# app_out_8x_16A_bistab_seperated_4MU_BOT_.net
KiCad netlist of a schematic drawn in EAGLE
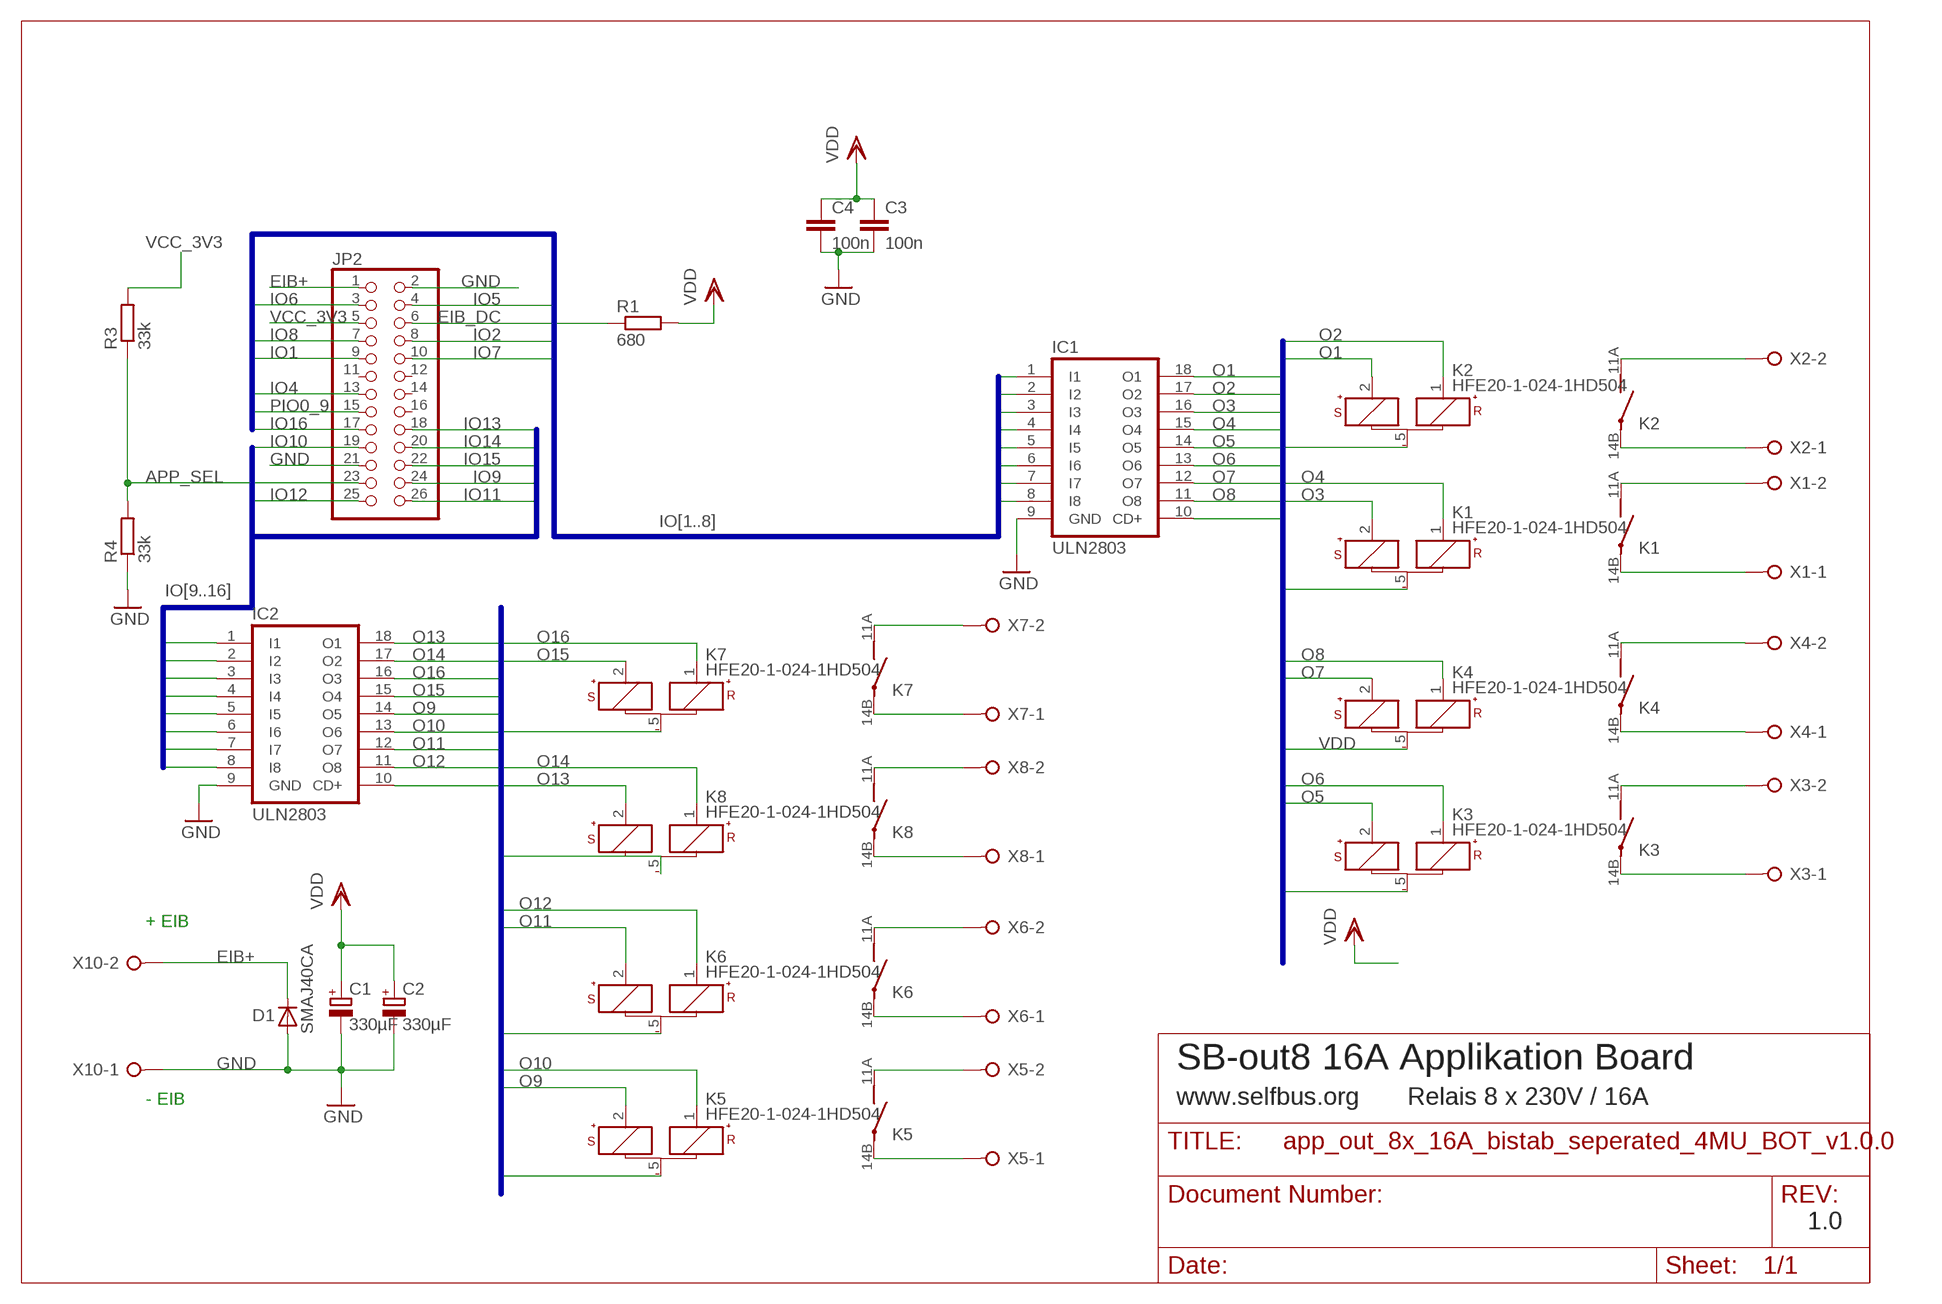
[diagram p0: schematic, sheet 1]

(export (version "E")
  (design (tool "Eeschema 10.0.6"))
  (components
    (comp (ref "C1")
      (value "330µF")
      (footprint "eagle-import:E3,5-8")
      (libsource (lib "eagle-import") (part "CPOL-EUE3.5-8"))
    )
    (comp (ref "C2")
      (value "330µF")
      (footprint "eagle-import:E3,5-8")
      (libsource (lib "eagle-import") (part "CPOL-EUE3.5-8"))
    )
    (comp (ref "C3")
      (value "100n")
      (footprint "eagle-import:C1206")
      (libsource (lib "eagle-import") (part "C-EUC1206"))
    )
    (comp (ref "C4")
      (value "100n")
      (footprint "eagle-import:C1206")
      (libsource (lib "eagle-import") (part "C-EUC1206"))
    )
    (comp (ref "D1")
      (value "SMAJ40CA")
      (footprint "eagle-import:SMB")
      (libsource (lib "eagle-import") (part "D-SMB"))
    )
    (comp (ref "IC1")
      (value "ULN2803")
      (footprint "eagle-import:SO18W")
      (libsource (lib "eagle-import") (part "ULN2803ASOP18"))
    )
    (comp (ref "IC2")
      (value "ULN2803")
      (footprint "eagle-import:SO18W")
      (libsource (lib "eagle-import") (part "ULN2803ASOP18"))
    )
    (comp (ref "JP2")
      (value "PINHD-2X13_2.54-SMD")
      (footprint "eagle-import:2X13SMD")
      (libsource (lib "eagle-import") (part "PINHD-2X13_2.54-SMD"))
    )
    (comp (ref "K1")
      (value "HFE20-1-024-1HD504")
      (footprint "eagle-import:HFE20-3-504")
      (libsource (lib "eagle-import") (part "HFE20-1-024-1HD504"))
    )
    (comp (ref "K2")
      (value "HFE20-1-024-1HD504")
      (footprint "eagle-import:HFE20-3-504")
      (libsource (lib "eagle-import") (part "HFE20-1-024-1HD504"))
    )
    (comp (ref "K3")
      (value "HFE20-1-024-1HD504")
      (footprint "eagle-import:HFE20-3-504")
      (libsource (lib "eagle-import") (part "HFE20-1-024-1HD504"))
    )
    (comp (ref "K4")
      (value "HFE20-1-024-1HD504")
      (footprint "eagle-import:HFE20-3-504")
      (libsource (lib "eagle-import") (part "HFE20-1-024-1HD504"))
    )
    (comp (ref "K5")
      (value "HFE20-1-024-1HD504")
      (footprint "eagle-import:HFE20-3-504")
      (libsource (lib "eagle-import") (part "HFE20-1-024-1HD504"))
    )
    (comp (ref "K6")
      (value "HFE20-1-024-1HD504")
      (footprint "eagle-import:HFE20-3-504")
      (libsource (lib "eagle-import") (part "HFE20-1-024-1HD504"))
    )
    (comp (ref "K7")
      (value "HFE20-1-024-1HD504")
      (footprint "eagle-import:HFE20-3-504")
      (libsource (lib "eagle-import") (part "HFE20-1-024-1HD504"))
    )
    (comp (ref "K8")
      (value "HFE20-1-024-1HD504")
      (footprint "eagle-import:HFE20-3-504")
      (libsource (lib "eagle-import") (part "HFE20-1-024-1HD504"))
    )
    (comp (ref "R1")
      (value "680")
      (footprint "eagle-import:M1206")
      (libsource (lib "eagle-import") (part "R-EU_M1206"))
    )
    (comp (ref "R3")
      (value "33k")
      (footprint "eagle-import:M1206")
      (libsource (lib "eagle-import") (part "R-EU_M1206"))
    )
    (comp (ref "R4")
      (value "33k")
      (footprint "eagle-import:M1206")
      (libsource (lib "eagle-import") (part "R-EU_M1206"))
    )
    (comp (ref "X1")
      (value "W237-02P")
      (footprint "eagle-import:W237-132")
      (libsource (lib "eagle-import") (part "W237-02P"))
    )
    (comp (ref "X2")
      (value "W237-02P")
      (footprint "eagle-import:W237-132")
      (libsource (lib "eagle-import") (part "W237-02P"))
    )
    (comp (ref "X3")
      (value "W237-02P")
      (footprint "eagle-import:W237-132")
      (libsource (lib "eagle-import") (part "W237-02P"))
    )
    (comp (ref "X4")
      (value "W237-02P")
      (footprint "eagle-import:W237-132")
      (libsource (lib "eagle-import") (part "W237-02P"))
    )
    (comp (ref "X5")
      (value "W237-02P")
      (footprint "eagle-import:W237-132")
      (libsource (lib "eagle-import") (part "W237-02P"))
    )
    (comp (ref "X6")
      (value "W237-02P")
      (footprint "eagle-import:W237-132")
      (libsource (lib "eagle-import") (part "W237-02P"))
    )
    (comp (ref "X7")
      (value "W237-02P")
      (footprint "eagle-import:W237-132")
      (libsource (lib "eagle-import") (part "W237-02P"))
    )
    (comp (ref "X8")
      (value "W237-02P")
      (footprint "eagle-import:W237-132")
      (libsource (lib "eagle-import") (part "W237-02P"))
    )
    (comp (ref "X10")
      (value "W237-02P")
      (footprint "eagle-import:W237-132")
      (libsource (lib "eagle-import") (part "W237-02P"))
    )
  )
  (nets
    (net (code "2") (name "/APP_SEL") (class "Default")
      (node (ref "JP2") (pin "23") (pinfunction "23_23") (pintype "passive"))
      (node (ref "R3") (pin "1") (pinfunction "1_1") (pintype "passive"))
      (node (ref "R4") (pin "2") (pinfunction "2_2") (pintype "passive"))
    )
    (net (code "3") (name "/EIB+") (class "Default")
      (node (ref "D1") (pin "1") (pinfunction "C_1") (pintype "passive"))
      (node (ref "JP2") (pin "1") (pinfunction "1_1") (pintype "passive"))
      (node (ref "X10") (pin "2") (pinfunction "KL_2") (pintype "passive"))
    )
    (net (code "4") (name "/EIB_DC") (class "Default")
      (node (ref "JP2") (pin "6") (pinfunction "6_6") (pintype "passive"))
      (node (ref "R1") (pin "1") (pinfunction "1_1") (pintype "passive"))
    )
    (net (code "5") (name "/IO1") (class "Default")
      (node (ref "IC1") (pin "5") (pinfunction "I5_5") (pintype "input"))
      (node (ref "JP2") (pin "9") (pinfunction "9_9") (pintype "passive"))
    )
    (net (code "6") (name "/IO2") (class "Default")
      (node (ref "IC1") (pin "4") (pinfunction "I4_4") (pintype "input"))
      (node (ref "JP2") (pin "8") (pinfunction "8_8") (pintype "passive"))
    )
    (net (code "7") (name "/IO4") (class "Default")
      (node (ref "IC1") (pin "8") (pinfunction "I8_8") (pintype "input"))
      (node (ref "JP2") (pin "13") (pinfunction "13_13") (pintype "passive"))
    )
    (net (code "8") (name "/IO5") (class "Default")
      (node (ref "IC1") (pin "1") (pinfunction "I1_1") (pintype "input"))
      (node (ref "JP2") (pin "4") (pinfunction "4_4") (pintype "passive"))
    )
    (net (code "9") (name "/IO6") (class "Default")
      (node (ref "IC1") (pin "2") (pinfunction "I2_2") (pintype "input"))
      (node (ref "JP2") (pin "3") (pinfunction "3_3") (pintype "passive"))
    )
    (net (code "10") (name "/IO7") (class "Default")
      (node (ref "IC1") (pin "6") (pinfunction "I6_6") (pintype "input"))
      (node (ref "JP2") (pin "10") (pinfunction "10_10") (pintype "passive"))
    )
    (net (code "11") (name "/IO8") (class "Default")
      (node (ref "IC1") (pin "3") (pinfunction "I3_3") (pintype "input"))
      (node (ref "JP2") (pin "7") (pinfunction "7_7") (pintype "passive"))
    )
    (net (code "12") (name "/IO9") (class "Default")
      (node (ref "IC2") (pin "5") (pinfunction "I5_5") (pintype "input"))
      (node (ref "JP2") (pin "24") (pinfunction "24_24") (pintype "passive"))
    )
    (net (code "13") (name "/IO10") (class "Default")
      (node (ref "IC2") (pin "6") (pinfunction "I6_6") (pintype "input"))
      (node (ref "JP2") (pin "19") (pinfunction "19_19") (pintype "passive"))
    )
    (net (code "14") (name "/IO11") (class "Default")
      (node (ref "IC2") (pin "7") (pinfunction "I7_7") (pintype "input"))
      (node (ref "JP2") (pin "26") (pinfunction "26_26") (pintype "passive"))
    )
    (net (code "15") (name "/IO12") (class "Default")
      (node (ref "IC2") (pin "8") (pinfunction "I8_8") (pintype "input"))
      (node (ref "JP2") (pin "25") (pinfunction "25_25") (pintype "passive"))
    )
    (net (code "16") (name "/IO13") (class "Default")
      (node (ref "IC2") (pin "1") (pinfunction "I1_1") (pintype "input"))
      (node (ref "JP2") (pin "18") (pinfunction "18_18") (pintype "passive"))
    )
    (net (code "17") (name "/IO14") (class "Default")
      (node (ref "IC2") (pin "2") (pinfunction "I2_2") (pintype "input"))
      (node (ref "JP2") (pin "20") (pinfunction "20_20") (pintype "passive"))
    )
    (net (code "18") (name "/IO15") (class "Default")
      (node (ref "IC2") (pin "4") (pinfunction "I4_4") (pintype "input"))
      (node (ref "JP2") (pin "22") (pinfunction "22_22") (pintype "passive"))
    )
    (net (code "19") (name "/IO16") (class "Default")
      (node (ref "IC2") (pin "3") (pinfunction "I3_3") (pintype "input"))
      (node (ref "JP2") (pin "17") (pinfunction "17_17") (pintype "passive"))
    )
    (net (code "22") (name "/O1") (class "Default")
      (node (ref "IC1") (pin "18") (pinfunction "O1_18") (pintype "open_collector"))
      (node (ref "K2") (pin "2") (pinfunction "S+_2") (pintype "passive"))
    )
    (net (code "23") (name "/O2") (class "Default")
      (node (ref "IC1") (pin "17") (pinfunction "O2_17") (pintype "open_collector"))
      (node (ref "K2") (pin "1") (pinfunction "R+_1") (pintype "passive"))
    )
    (net (code "24") (name "/O3") (class "Default")
      (node (ref "IC1") (pin "16") (pinfunction "O3_16") (pintype "open_collector"))
      (node (ref "K1") (pin "2") (pinfunction "S+_2") (pintype "passive"))
    )
    (net (code "25") (name "/O4") (class "Default")
      (node (ref "IC1") (pin "15") (pinfunction "O4_15") (pintype "open_collector"))
      (node (ref "K1") (pin "1") (pinfunction "R+_1") (pintype "passive"))
    )
    (net (code "26") (name "/O5") (class "Default")
      (node (ref "IC1") (pin "14") (pinfunction "O5_14") (pintype "open_collector"))
      (node (ref "K3") (pin "2") (pinfunction "S+_2") (pintype "passive"))
    )
    (net (code "27") (name "/O6") (class "Default")
      (node (ref "IC1") (pin "13") (pinfunction "O6_13") (pintype "open_collector"))
      (node (ref "K3") (pin "1") (pinfunction "R+_1") (pintype "passive"))
    )
    (net (code "28") (name "/O7") (class "Default")
      (node (ref "IC1") (pin "12") (pinfunction "O7_12") (pintype "open_collector"))
      (node (ref "K4") (pin "2") (pinfunction "S+_2") (pintype "passive"))
    )
    (net (code "29") (name "/O8") (class "Default")
      (node (ref "IC1") (pin "11") (pinfunction "O8_11") (pintype "open_collector"))
      (node (ref "K4") (pin "1") (pinfunction "R+_1") (pintype "passive"))
    )
    (net (code "30") (name "/O9") (class "Default")
      (node (ref "IC2") (pin "14") (pinfunction "O5_14") (pintype "open_collector"))
      (node (ref "K5") (pin "2") (pinfunction "S+_2") (pintype "passive"))
    )
    (net (code "31") (name "/O10") (class "Default")
      (node (ref "IC2") (pin "13") (pinfunction "O6_13") (pintype "open_collector"))
      (node (ref "K5") (pin "1") (pinfunction "R+_1") (pintype "passive"))
    )
    (net (code "32") (name "/O11") (class "Default")
      (node (ref "IC2") (pin "12") (pinfunction "O7_12") (pintype "open_collector"))
      (node (ref "K6") (pin "2") (pinfunction "S+_2") (pintype "passive"))
    )
    (net (code "33") (name "/O12") (class "Default")
      (node (ref "IC2") (pin "11") (pinfunction "O8_11") (pintype "open_collector"))
      (node (ref "K6") (pin "1") (pinfunction "R+_1") (pintype "passive"))
    )
    (net (code "34") (name "/O13") (class "Default")
      (node (ref "IC2") (pin "18") (pinfunction "O1_18") (pintype "open_collector"))
      (node (ref "K8") (pin "2") (pinfunction "S+_2") (pintype "passive"))
    )
    (net (code "35") (name "/O14") (class "Default")
      (node (ref "IC2") (pin "17") (pinfunction "O2_17") (pintype "open_collector"))
      (node (ref "K8") (pin "1") (pinfunction "R+_1") (pintype "passive"))
    )
    (net (code "36") (name "/O15") (class "Default")
      (node (ref "IC2") (pin "15") (pinfunction "O4_15") (pintype "open_collector"))
      (node (ref "K7") (pin "2") (pinfunction "S+_2") (pintype "passive"))
    )
    (net (code "37") (name "/O16") (class "Default")
      (node (ref "IC2") (pin "16") (pinfunction "O3_16") (pintype "open_collector"))
      (node (ref "K7") (pin "1") (pinfunction "R+_1") (pintype "passive"))
    )
    (net (code "38") (name "/PIO0_9") (class "Default")
      (node (ref "IC1") (pin "7") (pinfunction "I7_7") (pintype "input"))
      (node (ref "JP2") (pin "15") (pinfunction "15_15") (pintype "passive"))
    )
    (net (code "39") (name "/VCC_3V3") (class "Default")
      (node (ref "JP2") (pin "5") (pinfunction "5_5") (pintype "passive"))
      (node (ref "R3") (pin "2") (pinfunction "2_2") (pintype "passive"))
    )
    (net (code "40") (name "GND") (class "Default")
      (node (ref "C1") (pin "-") (pinfunction "-_-") (pintype "passive"))
      (node (ref "C2") (pin "-") (pinfunction "-_-") (pintype "passive"))
      (node (ref "C3") (pin "2") (pinfunction "2_2") (pintype "passive"))
      (node (ref "C4") (pin "2") (pinfunction "2_2") (pintype "passive"))
      (node (ref "D1") (pin "2") (pinfunction "A_2") (pintype "passive"))
      (node (ref "IC1") (pin "9") (pinfunction "GND_9") (pintype "power_in"))
      (node (ref "IC2") (pin "9") (pinfunction "GND_9") (pintype "power_in"))
      (node (ref "JP2") (pin "2") (pinfunction "2_2") (pintype "passive"))
      (node (ref "JP2") (pin "21") (pinfunction "21_21") (pintype "passive"))
      (node (ref "R4") (pin "1") (pinfunction "1_1") (pintype "passive"))
      (node (ref "X10") (pin "1") (pinfunction "KL_1") (pintype "passive"))
    )
    (net (code "41") (name "Net-(K1B-PA)") (class "Default")
      (node (ref "K1") (pin "14B") (pinfunction "PA_14B") (pintype "passive"))
      (node (ref "X1") (pin "1") (pinfunction "KL_1") (pintype "passive"))
    )
    (net (code "42") (name "Net-(K1B-PB)") (class "Default")
      (node (ref "K1") (pin "11A") (pinfunction "PB_11A") (pintype "passive"))
      (node (ref "X1") (pin "2") (pinfunction "KL_2") (pintype "passive"))
    )
    (net (code "43") (name "Net-(K2B-PA)") (class "Default")
      (node (ref "K2") (pin "14B") (pinfunction "PA_14B") (pintype "passive"))
      (node (ref "X2") (pin "1") (pinfunction "KL_1") (pintype "passive"))
    )
    (net (code "44") (name "Net-(K2B-PB)") (class "Default")
      (node (ref "K2") (pin "11A") (pinfunction "PB_11A") (pintype "passive"))
      (node (ref "X2") (pin "2") (pinfunction "KL_2") (pintype "passive"))
    )
    (net (code "45") (name "Net-(K3B-PA)") (class "Default")
      (node (ref "K3") (pin "14B") (pinfunction "PA_14B") (pintype "passive"))
      (node (ref "X3") (pin "1") (pinfunction "KL_1") (pintype "passive"))
    )
    (net (code "46") (name "Net-(K3B-PB)") (class "Default")
      (node (ref "K3") (pin "11A") (pinfunction "PB_11A") (pintype "passive"))
      (node (ref "X3") (pin "2") (pinfunction "KL_2") (pintype "passive"))
    )
    (net (code "47") (name "Net-(K4B-PA)") (class "Default")
      (node (ref "K4") (pin "14B") (pinfunction "PA_14B") (pintype "passive"))
      (node (ref "X4") (pin "1") (pinfunction "KL_1") (pintype "passive"))
    )
    (net (code "48") (name "Net-(K4B-PB)") (class "Default")
      (node (ref "K4") (pin "11A") (pinfunction "PB_11A") (pintype "passive"))
      (node (ref "X4") (pin "2") (pinfunction "KL_2") (pintype "passive"))
    )
    (net (code "49") (name "Net-(K5B-PA)") (class "Default")
      (node (ref "K5") (pin "14B") (pinfunction "PA_14B") (pintype "passive"))
      (node (ref "X5") (pin "1") (pinfunction "KL_1") (pintype "passive"))
    )
    (net (code "50") (name "Net-(K5B-PB)") (class "Default")
      (node (ref "K5") (pin "11A") (pinfunction "PB_11A") (pintype "passive"))
      (node (ref "X5") (pin "2") (pinfunction "KL_2") (pintype "passive"))
    )
    (net (code "51") (name "Net-(K6B-PA)") (class "Default")
      (node (ref "K6") (pin "14B") (pinfunction "PA_14B") (pintype "passive"))
      (node (ref "X6") (pin "1") (pinfunction "KL_1") (pintype "passive"))
    )
    (net (code "52") (name "Net-(K6B-PB)") (class "Default")
      (node (ref "K6") (pin "11A") (pinfunction "PB_11A") (pintype "passive"))
      (node (ref "X6") (pin "2") (pinfunction "KL_2") (pintype "passive"))
    )
    (net (code "53") (name "Net-(K7B-PA)") (class "Default")
      (node (ref "K7") (pin "14B") (pinfunction "PA_14B") (pintype "passive"))
      (node (ref "X7") (pin "1") (pinfunction "KL_1") (pintype "passive"))
    )
    (net (code "54") (name "Net-(K7B-PB)") (class "Default")
      (node (ref "K7") (pin "11A") (pinfunction "PB_11A") (pintype "passive"))
      (node (ref "X7") (pin "2") (pinfunction "KL_2") (pintype "passive"))
    )
    (net (code "55") (name "Net-(K8B-PA)") (class "Default")
      (node (ref "K8") (pin "14B") (pinfunction "PA_14B") (pintype "passive"))
      (node (ref "X8") (pin "1") (pinfunction "KL_1") (pintype "passive"))
    )
    (net (code "56") (name "Net-(K8B-PB)") (class "Default")
      (node (ref "K8") (pin "11A") (pinfunction "PB_11A") (pintype "passive"))
      (node (ref "X8") (pin "2") (pinfunction "KL_2") (pintype "passive"))
    )
    (net (code "57") (name "VDD") (class "Default")
      (node (ref "C1") (pin "+") (pinfunction "+_+") (pintype "passive"))
      (node (ref "C2") (pin "+") (pinfunction "+_+") (pintype "passive"))
      (node (ref "C3") (pin "1") (pinfunction "1_1") (pintype "passive"))
      (node (ref "C4") (pin "1") (pinfunction "1_1") (pintype "passive"))
      (node (ref "IC1") (pin "10") (pinfunction "CD+_10") (pintype "passive"))
      (node (ref "IC2") (pin "10") (pinfunction "CD+_10") (pintype "passive"))
      (node (ref "K1") (pin "5") (pinfunction "-_5") (pintype "passive"))
      (node (ref "K2") (pin "5") (pinfunction "-_5") (pintype "passive"))
      (node (ref "K3") (pin "5") (pinfunction "-_5") (pintype "passive"))
      (node (ref "K4") (pin "5") (pinfunction "-_5") (pintype "passive"))
      (node (ref "K5") (pin "5") (pinfunction "-_5") (pintype "passive"))
      (node (ref "K6") (pin "5") (pinfunction "-_5") (pintype "passive"))
      (node (ref "K7") (pin "5") (pinfunction "-_5") (pintype "passive"))
      (node (ref "K8") (pin "5") (pinfunction "-_5") (pintype "passive"))
      (node (ref "R1") (pin "2") (pinfunction "2_2") (pintype "passive"))
    )
    (net (code "58") (name "unconnected-(JP2-Pad11)") (class "Default")
      (node (ref "JP2") (pin "11") (pinfunction "11_11") (pintype "passive"))
    )
    (net (code "59") (name "unconnected-(JP2-Pad12)") (class "Default")
      (node (ref "JP2") (pin "12") (pinfunction "12_12") (pintype "passive"))
    )
    (net (code "60") (name "unconnected-(JP2-Pad14)") (class "Default")
      (node (ref "JP2") (pin "14") (pinfunction "14_14") (pintype "passive"))
    )
    (net (code "61") (name "unconnected-(JP2-Pad16)") (class "Default")
      (node (ref "JP2") (pin "16") (pinfunction "16_16") (pintype "passive"))
    )
  )
)
